# Output_Stage_v4.net
KiCad netlist of a schematic drawn in EAGLE
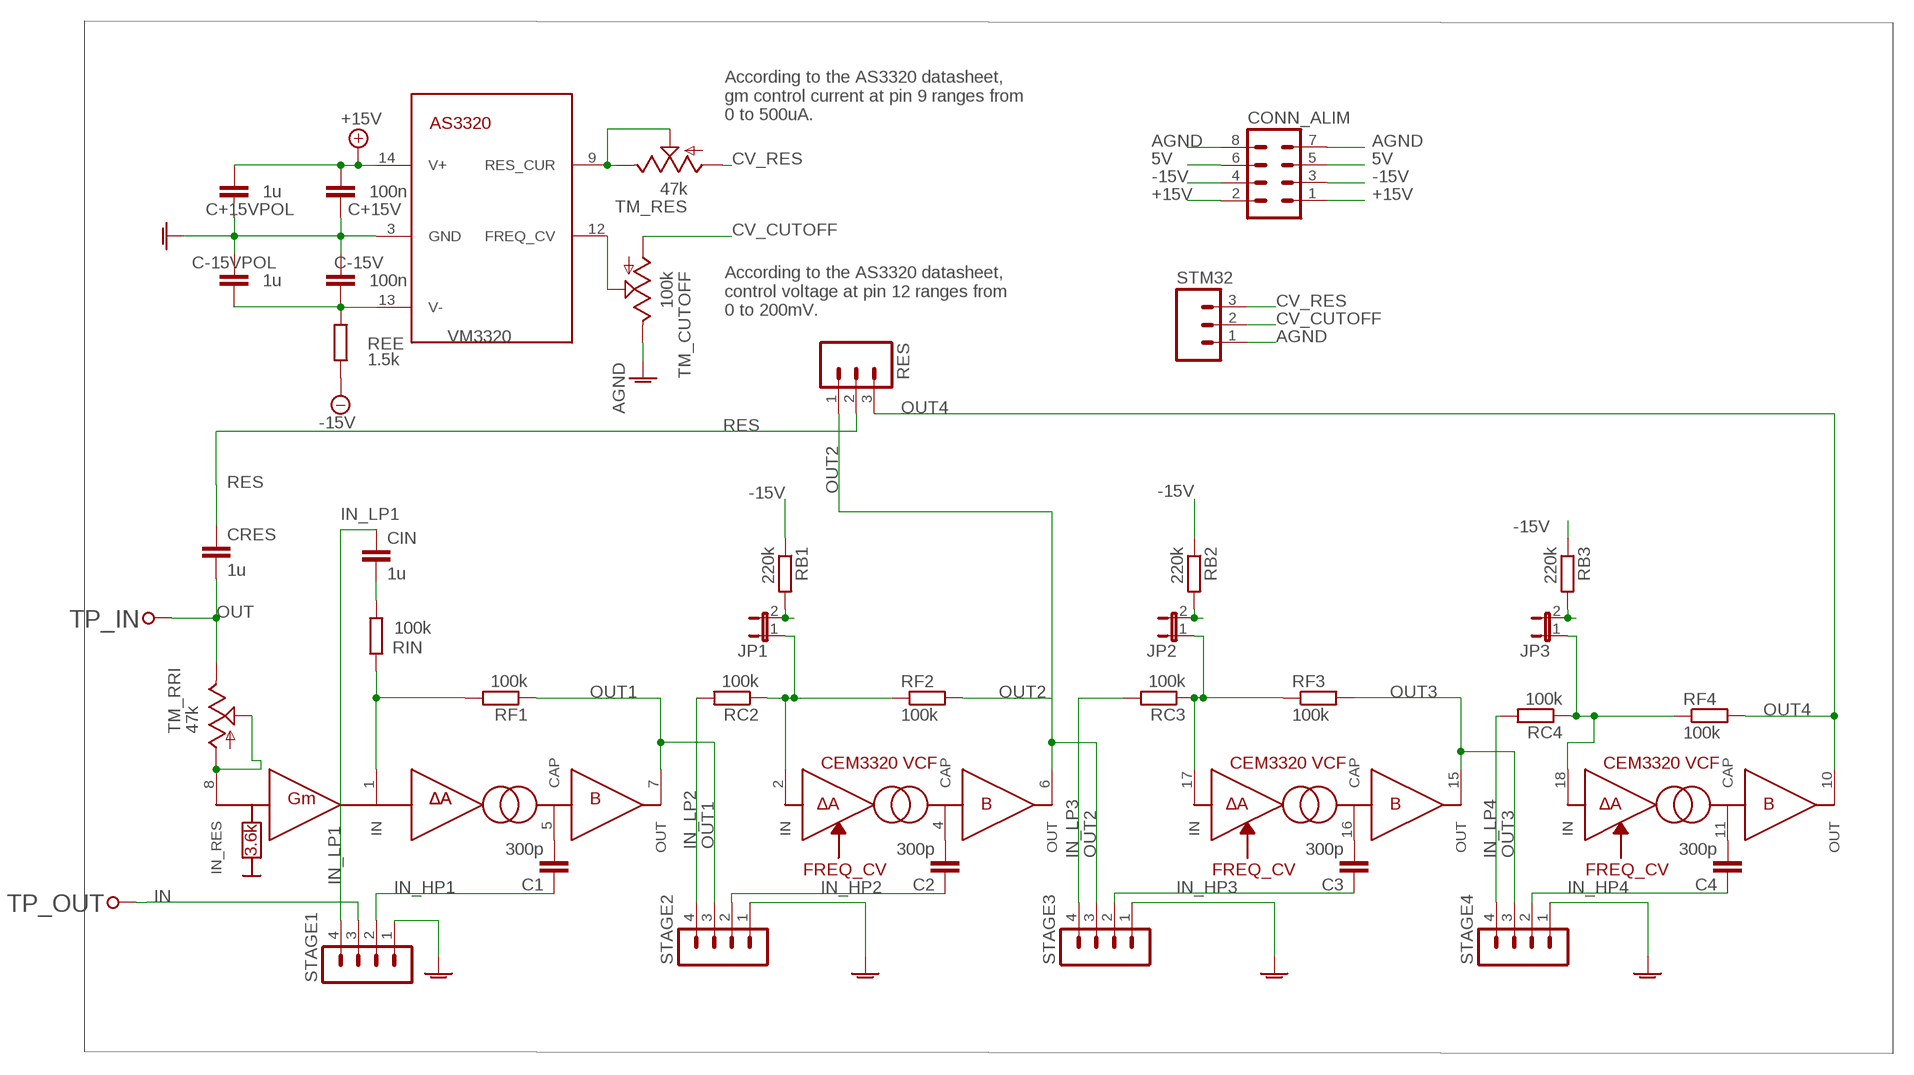
[diagram p0: schematic, sheet 1]

(export (version "E")
  (design (tool "Eeschema 10.0.6"))
  (components
    (comp (ref "C+15V")
      (value "100n")
      (footprint "eagle-import:C050-050X075")
      (libsource (lib "eagle-import") (part "C-EU050-050X075"))
    )
    (comp (ref "C+15VPOL")
      (value "1u")
      (footprint "eagle-import:C050-050X075")
      (libsource (lib "eagle-import") (part "C-EU050-050X075"))
    )
    (comp (ref "C-15V")
      (value "100n")
      (footprint "eagle-import:C050-050X075")
      (libsource (lib "eagle-import") (part "C-EU050-050X075"))
    )
    (comp (ref "C-15VPOL")
      (value "1u")
      (footprint "eagle-import:C050-050X075")
      (libsource (lib "eagle-import") (part "C-EU050-050X075"))
    )
    (comp (ref "C1")
      (value "300p")
      (footprint "eagle-import:C050-030X075")
      (libsource (lib "eagle-import") (part "C-EU050-030X075"))
    )
    (comp (ref "C2")
      (value "300p")
      (footprint "eagle-import:C075-032X103")
      (libsource (lib "eagle-import") (part "C-EU075-032X103"))
    )
    (comp (ref "C3")
      (value "300p")
      (footprint "eagle-import:C050-030X075")
      (libsource (lib "eagle-import") (part "C-EU050-030X075"))
    )
    (comp (ref "C4")
      (value "300p")
      (footprint "eagle-import:C050-030X075")
      (libsource (lib "eagle-import") (part "C-EU050-030X075"))
    )
    (comp (ref "CIN")
      (value "1u")
      (footprint "eagle-import:C050-030X075")
      (libsource (lib "eagle-import") (part "C-EU050-030X075"))
    )
    (comp (ref "CONN_ALIM")
      (value "MA04-2")
      (footprint "eagle-import:MA04-2")
      (libsource (lib "eagle-import") (part "MA04-2"))
    )
    (comp (ref "CRES")
      (value "1u")
      (footprint "eagle-import:C050-030X075")
      (libsource (lib "eagle-import") (part "C-EU050-030X075"))
    )
    (comp (ref "JP1")
      (value "JP1E")
      (footprint "eagle-import:JP1")
      (libsource (lib "eagle-import") (part "JP1E"))
    )
    (comp (ref "JP2")
      (value "JP1E")
      (footprint "eagle-import:JP1")
      (libsource (lib "eagle-import") (part "JP1E"))
    )
    (comp (ref "JP3")
      (value "JP1E")
      (footprint "eagle-import:JP1")
      (libsource (lib "eagle-import") (part "JP1E"))
    )
    (comp (ref "RB1")
      (value "220k")
      (footprint "eagle-import:0204_7")
      (libsource (lib "eagle-import") (part "R-EU_0204/7"))
    )
    (comp (ref "RB2")
      (value "220k")
      (footprint "eagle-import:0204_7")
      (libsource (lib "eagle-import") (part "R-EU_0204/7"))
    )
    (comp (ref "RB3")
      (value "220k")
      (footprint "eagle-import:0204_7")
      (libsource (lib "eagle-import") (part "R-EU_0204/7"))
    )
    (comp (ref "RC2")
      (value "100k")
      (footprint "eagle-import:0204_7")
      (libsource (lib "eagle-import") (part "R-EU_0204/7"))
    )
    (comp (ref "RC3")
      (value "100k")
      (footprint "eagle-import:0204_7")
      (libsource (lib "eagle-import") (part "R-EU_0204/7"))
    )
    (comp (ref "RC4")
      (value "100k")
      (footprint "eagle-import:0204_7")
      (libsource (lib "eagle-import") (part "R-EU_0204/7"))
    )
    (comp (ref "REE")
      (value "1.5k")
      (footprint "eagle-import:0207_7")
      (libsource (lib "eagle-import") (part "R-EU_0207/7"))
    )
    (comp (ref "RES")
      (value "MA03")
      (footprint "eagle-import:03P")
      (libsource (lib "eagle-import") (part "MA03"))
    )
    (comp (ref "RF1")
      (value "100k")
      (footprint "eagle-import:0204_7")
      (libsource (lib "eagle-import") (part "R-EU_0204/7"))
    )
    (comp (ref "RF2")
      (value "100k")
      (footprint "eagle-import:0204_7")
      (libsource (lib "eagle-import") (part "R-EU_0204/7"))
    )
    (comp (ref "RF3")
      (value "100k")
      (footprint "eagle-import:0204_7")
      (libsource (lib "eagle-import") (part "R-EU_0204/7"))
    )
    (comp (ref "RF4")
      (value "100k")
      (footprint "eagle-import:0204_7")
      (libsource (lib "eagle-import") (part "R-EU_0204/7"))
    )
    (comp (ref "RIN")
      (value "100k")
      (footprint "eagle-import:0204_7")
      (libsource (lib "eagle-import") (part "R-EU_0204/7"))
    )
    (comp (ref "STAGE1")
      (value "MA04-1")
      (footprint "eagle-import:MA04-1")
      (libsource (lib "eagle-import") (part "MA04-1"))
    )
    (comp (ref "STAGE2")
      (value "MA04-1")
      (footprint "eagle-import:MA04-1")
      (libsource (lib "eagle-import") (part "MA04-1"))
    )
    (comp (ref "STAGE3")
      (value "MA04-1")
      (footprint "eagle-import:MA04-1")
      (libsource (lib "eagle-import") (part "MA04-1"))
    )
    (comp (ref "STAGE4")
      (value "MA04-1")
      (footprint "eagle-import:MA04-1")
      (libsource (lib "eagle-import") (part "MA04-1"))
    )
    (comp (ref "STM32")
      (value "MA03")
      (footprint "eagle-import:03P")
      (libsource (lib "eagle-import") (part "MA03"))
    )
    (comp (ref "TM_CUTOFF")
      (value "100k")
      (footprint "eagle-import:6MM")
      (libsource (lib "eagle-import") (part "TRIM"))
    )
    (comp (ref "TM_RES")
      (value "47k")
      (footprint "eagle-import:6MM")
      (libsource (lib "eagle-import") (part "TRIM"))
    )
    (comp (ref "TM_RRI")
      (value "47k")
      (footprint "eagle-import:6MM")
      (libsource (lib "eagle-import") (part "TRIM"))
    )
    (comp (ref "TP_IN")
      (value "TESTPOINT")
      (footprint "eagle-import:TESTPOINT_63")
      (libsource (lib "eagle-import") (part "TESTPOINT"))
    )
    (comp (ref "TP_OUT")
      (value "TESTPOINT")
      (footprint "eagle-import:TESTPOINT_63")
      (libsource (lib "eagle-import") (part "TESTPOINT"))
    )
    (comp (ref "VCF")
      (value "AS3320")
      (footprint "eagle-import:DIL18")
      (libsource (lib "eagle-import") (part "AS3320"))
    )
  )
  (nets
    (net (code "1") (name "+15V") (class "Default")
      (node (ref "C+15V") (pin "2") (pinfunction "2_2") (pintype "passive"))
      (node (ref "C+15VPOL") (pin "2") (pinfunction "2_2") (pintype "passive"))
      (node (ref "CONN_ALIM") (pin "1") (pinfunction "1_1") (pintype "passive"))
      (node (ref "CONN_ALIM") (pin "2") (pinfunction "2_2") (pintype "passive"))
      (node (ref "VCF") (pin "14") (pinfunction "V+_14") (pintype "bidirectional"))
    )
    (net (code "2") (name "-15V") (class "Default")
      (node (ref "CONN_ALIM") (pin "3") (pinfunction "3_3") (pintype "passive"))
      (node (ref "CONN_ALIM") (pin "4") (pinfunction "4_4") (pintype "passive"))
      (node (ref "RB1") (pin "1") (pinfunction "1_1") (pintype "passive"))
      (node (ref "RB2") (pin "1") (pinfunction "1_1") (pintype "passive"))
      (node (ref "RB3") (pin "1") (pinfunction "1_1") (pintype "passive"))
      (node (ref "REE") (pin "1") (pinfunction "1_1") (pintype "passive"))
    )
    (net (code "3") (name "/5V") (class "Default")
      (node (ref "CONN_ALIM") (pin "5") (pinfunction "5_5") (pintype "passive"))
      (node (ref "CONN_ALIM") (pin "6") (pinfunction "6_6") (pintype "passive"))
    )
    (net (code "4") (name "/CV_CUTOFF") (class "Default")
      (node (ref "STM32") (pin "2") (pinfunction "2_2") (pintype "passive"))
      (node (ref "TM_CUTOFF") (pin "A") (pinfunction "A_A") (pintype "passive"))
    )
    (net (code "5") (name "/CV_RES") (class "Default")
      (node (ref "STM32") (pin "3") (pinfunction "3_3") (pintype "passive"))
      (node (ref "TM_RES") (pin "A") (pinfunction "A_A") (pintype "passive"))
    )
    (net (code "6") (name "/IN") (class "Default")
      (node (ref "STAGE1") (pin "3") (pinfunction "3_3") (pintype "passive"))
      (node (ref "TP_OUT") (pin "P$1") (pinfunction "P$1_P$1") (pintype "passive"))
    )
    (net (code "7") (name "/IN_HP1") (class "Default")
      (node (ref "C1") (pin "1") (pinfunction "1_1") (pintype "passive"))
      (node (ref "STAGE1") (pin "2") (pinfunction "2_2") (pintype "passive"))
    )
    (net (code "8") (name "/IN_HP2") (class "Default")
      (node (ref "C2") (pin "1") (pinfunction "1_1") (pintype "passive"))
      (node (ref "STAGE2") (pin "2") (pinfunction "2_2") (pintype "passive"))
    )
    (net (code "9") (name "/IN_HP3") (class "Default")
      (node (ref "C3") (pin "1") (pinfunction "1_1") (pintype "passive"))
      (node (ref "STAGE3") (pin "2") (pinfunction "2_2") (pintype "passive"))
    )
    (net (code "10") (name "/IN_HP4") (class "Default")
      (node (ref "C4") (pin "1") (pinfunction "1_1") (pintype "passive"))
      (node (ref "STAGE4") (pin "2") (pinfunction "2_2") (pintype "passive"))
    )
    (net (code "11") (name "/IN_LP1") (class "Default")
      (node (ref "CIN") (pin "1") (pinfunction "1_1") (pintype "passive"))
      (node (ref "STAGE1") (pin "4") (pinfunction "4_4") (pintype "passive"))
    )
    (net (code "12") (name "/IN_LP2") (class "Default")
      (node (ref "RC2") (pin "2") (pinfunction "2_2") (pintype "passive"))
      (node (ref "STAGE2") (pin "4") (pinfunction "4_4") (pintype "passive"))
    )
    (net (code "13") (name "/IN_LP3") (class "Default")
      (node (ref "RC3") (pin "2") (pinfunction "2_2") (pintype "passive"))
      (node (ref "STAGE3") (pin "4") (pinfunction "4_4") (pintype "passive"))
    )
    (net (code "14") (name "/IN_LP4") (class "Default")
      (node (ref "RC4") (pin "2") (pinfunction "2_2") (pintype "passive"))
      (node (ref "STAGE4") (pin "4") (pinfunction "4_4") (pintype "passive"))
    )
    (net (code "15") (name "/OUT") (class "Default")
      (node (ref "CRES") (pin "2") (pinfunction "2_2") (pintype "passive"))
      (node (ref "TM_RRI") (pin "E") (pinfunction "E_E") (pintype "passive"))
      (node (ref "TP_IN") (pin "P$1") (pinfunction "P$1_P$1") (pintype "passive"))
    )
    (net (code "16") (name "/OUT1") (class "Default")
      (node (ref "RF1") (pin "1") (pinfunction "1_1") (pintype "passive"))
      (node (ref "STAGE2") (pin "3") (pinfunction "3_3") (pintype "passive"))
      (node (ref "VCF") (pin "7") (pinfunction "OUT_7") (pintype "bidirectional"))
    )
    (net (code "17") (name "/OUT2") (class "Default")
      (node (ref "RES") (pin "1") (pinfunction "1_1") (pintype "passive"))
      (node (ref "RF2") (pin "2") (pinfunction "2_2") (pintype "passive"))
      (node (ref "STAGE3") (pin "3") (pinfunction "3_3") (pintype "passive"))
      (node (ref "VCF") (pin "6") (pinfunction "OUT_6") (pintype "bidirectional"))
    )
    (net (code "18") (name "/OUT3") (class "Default")
      (node (ref "RF3") (pin "2") (pinfunction "2_2") (pintype "passive"))
      (node (ref "STAGE4") (pin "3") (pinfunction "3_3") (pintype "passive"))
      (node (ref "VCF") (pin "15") (pinfunction "OUT_15") (pintype "bidirectional"))
    )
    (net (code "19") (name "/OUT4") (class "Default")
      (node (ref "RES") (pin "3") (pinfunction "3_3") (pintype "passive"))
      (node (ref "RF4") (pin "2") (pinfunction "2_2") (pintype "passive"))
      (node (ref "VCF") (pin "10") (pinfunction "OUT_10") (pintype "bidirectional"))
    )
    (net (code "20") (name "/RES") (class "Default")
      (node (ref "CRES") (pin "1") (pinfunction "1_1") (pintype "passive"))
      (node (ref "RES") (pin "2") (pinfunction "2_2") (pintype "passive"))
    )
    (net (code "21") (name "/VM3320") (class "Default")
      (node (ref "C-15V") (pin "1") (pinfunction "1_1") (pintype "passive"))
      (node (ref "C-15VPOL") (pin "1") (pinfunction "1_1") (pintype "passive"))
      (node (ref "REE") (pin "2") (pinfunction "2_2") (pintype "passive"))
      (node (ref "VCF") (pin "13") (pinfunction "V-_13") (pintype "bidirectional"))
    )
    (net (code "22") (name "AGND") (class "Default")
      (node (ref "C+15V") (pin "1") (pinfunction "1_1") (pintype "passive"))
      (node (ref "C+15VPOL") (pin "1") (pinfunction "1_1") (pintype "passive"))
      (node (ref "C-15V") (pin "2") (pinfunction "2_2") (pintype "passive"))
      (node (ref "C-15VPOL") (pin "2") (pinfunction "2_2") (pintype "passive"))
      (node (ref "CONN_ALIM") (pin "7") (pinfunction "7_7") (pintype "passive"))
      (node (ref "CONN_ALIM") (pin "8") (pinfunction "8_8") (pintype "passive"))
      (node (ref "STAGE1") (pin "1") (pinfunction "1_1") (pintype "passive"))
      (node (ref "STAGE2") (pin "1") (pinfunction "1_1") (pintype "passive"))
      (node (ref "STAGE3") (pin "1") (pinfunction "1_1") (pintype "passive"))
      (node (ref "STAGE4") (pin "1") (pinfunction "1_1") (pintype "passive"))
      (node (ref "STM32") (pin "1") (pinfunction "1_1") (pintype "passive"))
      (node (ref "TM_CUTOFF") (pin "E") (pinfunction "E_E") (pintype "passive"))
      (node (ref "VCF") (pin "3") (pinfunction "GND_3") (pintype "bidirectional"))
    )
    (net (code "23") (name "Net-(CIN-Pad2)") (class "Default")
      (node (ref "CIN") (pin "2") (pinfunction "2_2") (pintype "passive"))
      (node (ref "RIN") (pin "1") (pinfunction "1_1") (pintype "passive"))
    )
    (net (code "24") (name "Net-(JP1-Pad2)") (class "Default")
      (node (ref "JP1") (pin "2") (pinfunction "2_2") (pintype "passive"))
      (node (ref "RB1") (pin "2") (pinfunction "2_2") (pintype "passive"))
    )
    (net (code "25") (name "Net-(JP2-Pad2)") (class "Default")
      (node (ref "JP2") (pin "2") (pinfunction "2_2") (pintype "passive"))
      (node (ref "RB2") (pin "2") (pinfunction "2_2") (pintype "passive"))
    )
    (net (code "26") (name "Net-(JP3-Pad2)") (class "Default")
      (node (ref "JP3") (pin "2") (pinfunction "2_2") (pintype "passive"))
      (node (ref "RB3") (pin "2") (pinfunction "2_2") (pintype "passive"))
    )
    (net (code "27") (name "Net-(VCFA-CAP)") (class "Default")
      (node (ref "C1") (pin "2") (pinfunction "2_2") (pintype "passive"))
      (node (ref "VCF") (pin "5") (pinfunction "CAP_5") (pintype "bidirectional"))
    )
    (net (code "28") (name "Net-(VCFA-IN)") (class "Default")
      (node (ref "RF1") (pin "2") (pinfunction "2_2") (pintype "passive"))
      (node (ref "RIN") (pin "2") (pinfunction "2_2") (pintype "passive"))
      (node (ref "VCF") (pin "1") (pinfunction "IN_1") (pintype "bidirectional"))
    )
    (net (code "29") (name "Net-(VCFA-IN_RES)") (class "Default")
      (node (ref "TM_RRI") (pin "A") (pinfunction "A_A") (pintype "passive"))
      (node (ref "TM_RRI") (pin "S") (pinfunction "S_S") (pintype "passive"))
      (node (ref "VCF") (pin "8") (pinfunction "IN_RES_8") (pintype "bidirectional"))
    )
    (net (code "30") (name "Net-(VCFB-CAP)") (class "Default")
      (node (ref "C2") (pin "2") (pinfunction "2_2") (pintype "passive"))
      (node (ref "VCF") (pin "4") (pinfunction "CAP_4") (pintype "bidirectional"))
    )
    (net (code "31") (name "Net-(VCFB-IN)") (class "Default")
      (node (ref "JP1") (pin "1") (pinfunction "1_1") (pintype "passive"))
      (node (ref "RC2") (pin "1") (pinfunction "1_1") (pintype "passive"))
      (node (ref "RF2") (pin "1") (pinfunction "1_1") (pintype "passive"))
      (node (ref "VCF") (pin "2") (pinfunction "IN_2") (pintype "bidirectional"))
    )
    (net (code "32") (name "Net-(VCFC-CAP)") (class "Default")
      (node (ref "C4") (pin "2") (pinfunction "2_2") (pintype "passive"))
      (node (ref "VCF") (pin "11") (pinfunction "CAP_11") (pintype "bidirectional"))
    )
    (net (code "33") (name "Net-(VCFC-IN)") (class "Default")
      (node (ref "JP3") (pin "1") (pinfunction "1_1") (pintype "passive"))
      (node (ref "RC4") (pin "1") (pinfunction "1_1") (pintype "passive"))
      (node (ref "RF4") (pin "1") (pinfunction "1_1") (pintype "passive"))
      (node (ref "VCF") (pin "18") (pinfunction "IN_18") (pintype "bidirectional"))
    )
    (net (code "34") (name "Net-(VCFD-CAP)") (class "Default")
      (node (ref "C3") (pin "2") (pinfunction "2_2") (pintype "passive"))
      (node (ref "VCF") (pin "16") (pinfunction "CAP_16") (pintype "bidirectional"))
    )
    (net (code "35") (name "Net-(VCFD-IN)") (class "Default")
      (node (ref "JP2") (pin "1") (pinfunction "1_1") (pintype "passive"))
      (node (ref "RC3") (pin "1") (pinfunction "1_1") (pintype "passive"))
      (node (ref "RF3") (pin "1") (pinfunction "1_1") (pintype "passive"))
      (node (ref "VCF") (pin "17") (pinfunction "IN_17") (pintype "bidirectional"))
    )
    (net (code "36") (name "Net-(VCFE-FREQ_CV)") (class "Default")
      (node (ref "TM_CUTOFF") (pin "S") (pinfunction "S_S") (pintype "passive"))
      (node (ref "VCF") (pin "12") (pinfunction "FREQ_CV_12") (pintype "bidirectional"))
    )
    (net (code "37") (name "Net-(VCFE-RES_CUR)") (class "Default")
      (node (ref "TM_RES") (pin "E") (pinfunction "E_E") (pintype "passive"))
      (node (ref "TM_RES") (pin "S") (pinfunction "S_S") (pintype "passive"))
      (node (ref "VCF") (pin "9") (pinfunction "RES_CUR_9") (pintype "bidirectional"))
    )
  )
)
